# SCH-1.net
KiCad netlist of a schematic drawn in Altium Designer
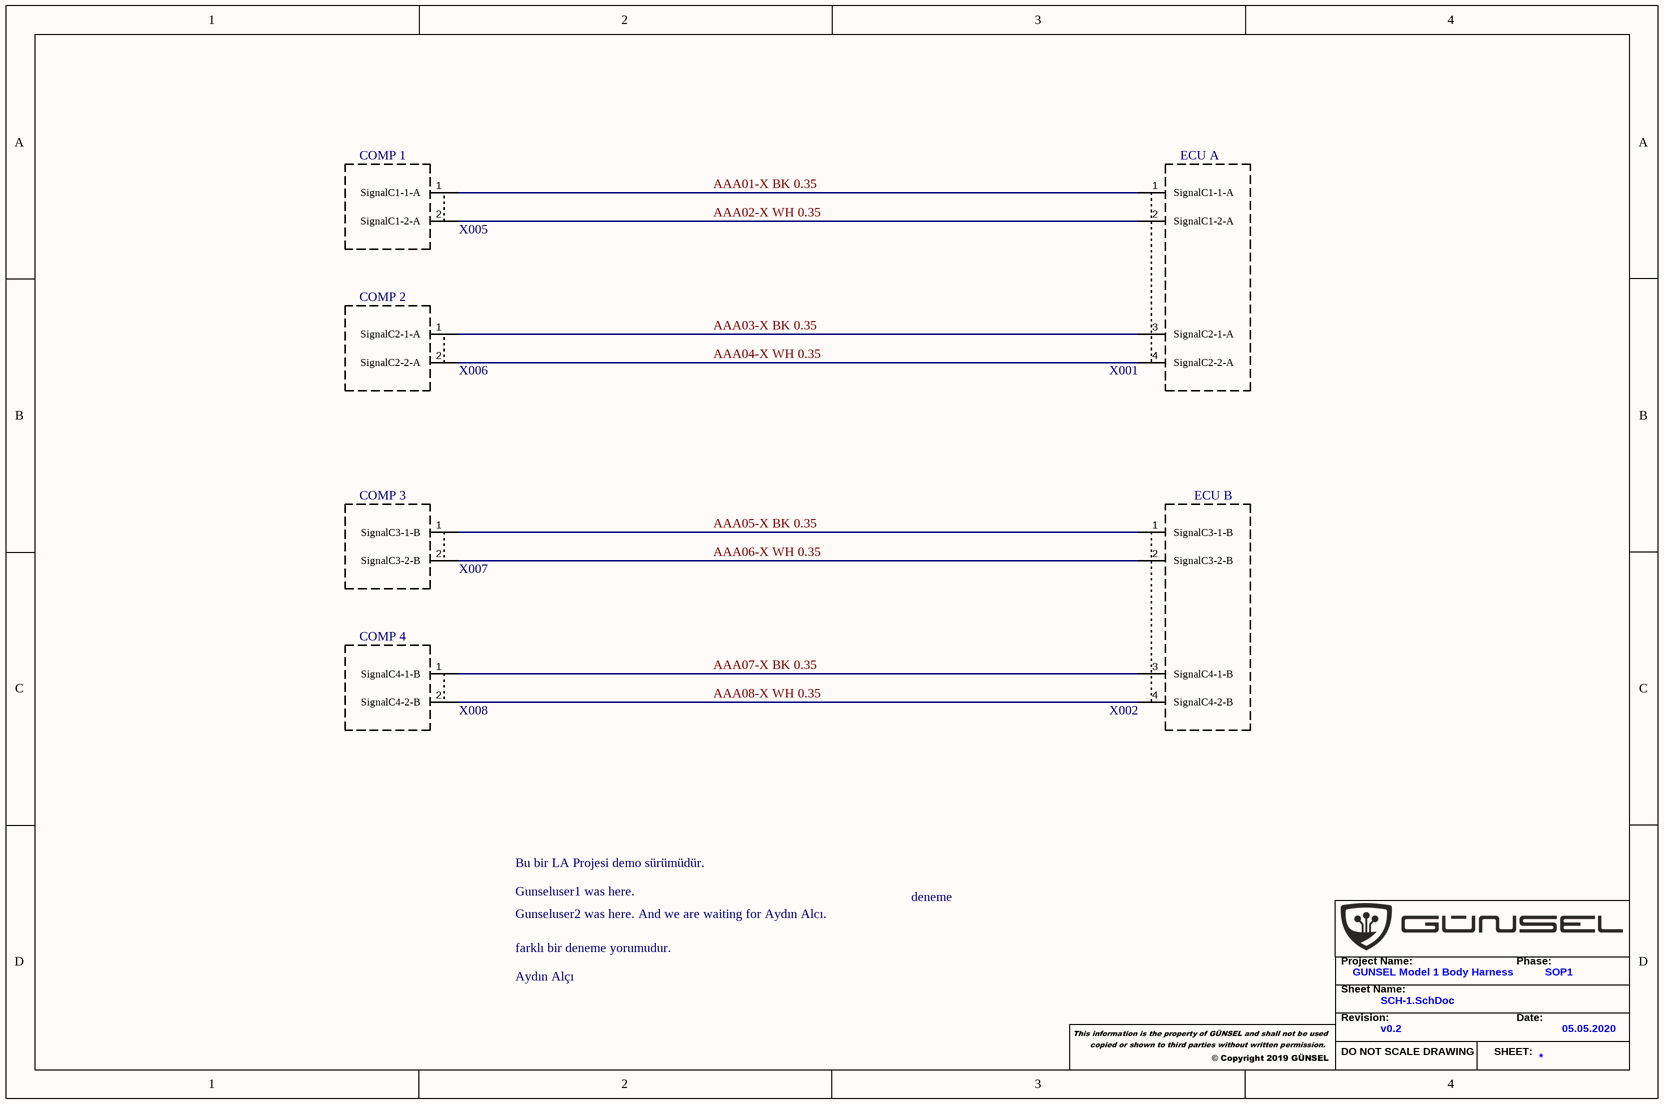
[diagram p0: SCH-1.SchDoc]

(export (version "E")
  (design (tool "Eeschema 10.0.6"))
  (components
    (comp (ref "X1")
      (value "X001")
      (fields (field (name "MANUFACTURER PART NUMBER") "E-1"))
      (libsource (lib "Günsel B9 LA Project Database Library") (part "E-1"))
    )
    (comp (ref "X2")
      (value "X005")
      (fields (field (name "MANUFACTURER PART NUMBER") "C-1"))
      (libsource (lib "Günsel B9 LA Project Database Library") (part "C-1"))
    )
    (comp (ref "X3")
      (value "X006")
      (fields (field (name "MANUFACTURER PART NUMBER") "C-2"))
      (libsource (lib "Günsel B9 LA Project Database Library") (part "C-2"))
    )
    (comp (ref "X4")
      (value "X002")
      (fields (field (name "MANUFACTURER PART NUMBER") "E-2"))
      (libsource (lib "Günsel B9 LA Project Database Library") (part "E-2"))
    )
    (comp (ref "X5")
      (value "X007")
      (fields (field (name "MANUFACTURER PART NUMBER") "C-3"))
      (libsource (lib "Günsel B9 LA Project Database Library") (part "C-3"))
    )
    (comp (ref "X6")
      (value "X008")
      (fields (field (name "MANUFACTURER PART NUMBER") "C-4"))
      (libsource (lib "Günsel B9 LA Project Database Library") (part "C-4"))
    )
  )
  (nets
    (net (code "1") (name "/AAA01-X BK 0.35") (class "Default")
      (node (ref "X1") (pin "1") (pinfunction "SignalC1-1-A_1") (pintype "passive"))
      (node (ref "X2") (pin "1") (pinfunction "SignalC1-1-A_1") (pintype "passive"))
    )
    (net (code "2") (name "/AAA02-X WH 0.35") (class "Default")
      (node (ref "X1") (pin "2") (pinfunction "SignalC1-2-A_2") (pintype "passive"))
      (node (ref "X2") (pin "2") (pinfunction "SignalC1-2-A_2") (pintype "passive"))
    )
    (net (code "3") (name "/AAA03-X BK 0.35") (class "Default")
      (node (ref "X1") (pin "3") (pinfunction "SignalC2-1-A_3") (pintype "passive"))
      (node (ref "X3") (pin "1") (pinfunction "SignalC2-1-A_1") (pintype "passive"))
    )
    (net (code "4") (name "/AAA04-X WH 0.35") (class "Default")
      (node (ref "X1") (pin "4") (pinfunction "SignalC2-2-A_4") (pintype "passive"))
      (node (ref "X3") (pin "2") (pinfunction "SignalC2-2-A_2") (pintype "passive"))
    )
    (net (code "5") (name "/AAA05-X BK 0.35") (class "Default")
      (node (ref "X4") (pin "1") (pinfunction "SignalC3-1-B_1") (pintype "passive"))
      (node (ref "X5") (pin "1") (pinfunction "SignalC3-1-B_1") (pintype "passive"))
    )
    (net (code "6") (name "/AAA06-X WH 0.35") (class "Default")
      (node (ref "X4") (pin "2") (pinfunction "SignalC3-2-B_2") (pintype "passive"))
      (node (ref "X5") (pin "2") (pinfunction "SignalC3-2-B_2") (pintype "passive"))
    )
    (net (code "7") (name "/AAA07-X BK 0.35") (class "Default")
      (node (ref "X4") (pin "3") (pinfunction "SignalC4-1-B_3") (pintype "passive"))
      (node (ref "X6") (pin "1") (pinfunction "SignalC4-1-B_1") (pintype "passive"))
    )
    (net (code "8") (name "/AAA08-X WH 0.35") (class "Default")
      (node (ref "X4") (pin "4") (pinfunction "SignalC4-2-B_4") (pintype "passive"))
      (node (ref "X6") (pin "2") (pinfunction "SignalC4-2-B_2") (pintype "passive"))
    )
    (net (code "9") (name "unconnected-(X1-Pad5)") (class "Default")
      (node (ref "X1") (pin "5") (pintype "passive"))
    )
    (net (code "10") (name "unconnected-(X1-Pad6)") (class "Default")
      (node (ref "X1") (pin "6") (pintype "passive"))
    )
    (net (code "11") (name "unconnected-(X1-Pad7)") (class "Default")
      (node (ref "X1") (pin "7") (pintype "passive"))
    )
    (net (code "12") (name "unconnected-(X1-Pad8)") (class "Default")
      (node (ref "X1") (pin "8") (pintype "passive"))
    )
    (net (code "13") (name "unconnected-(X1-Pad9)") (class "Default")
      (node (ref "X1") (pin "9") (pintype "passive"))
    )
    (net (code "14") (name "unconnected-(X1-Pad10)") (class "Default")
      (node (ref "X1") (pin "10") (pintype "passive"))
    )
    (net (code "15") (name "unconnected-(X1-Pad11)") (class "Default")
      (node (ref "X1") (pin "11") (pintype "passive"))
    )
    (net (code "16") (name "unconnected-(X1-Pad12)") (class "Default")
      (node (ref "X1") (pin "12") (pintype "passive"))
    )
    (net (code "17") (name "unconnected-(X1-Pad13)") (class "Default")
      (node (ref "X1") (pin "13") (pintype "passive"))
    )
    (net (code "18") (name "unconnected-(X1-Pad14)") (class "Default")
      (node (ref "X1") (pin "14") (pintype "passive"))
    )
    (net (code "19") (name "unconnected-(X1-Pad15)") (class "Default")
      (node (ref "X1") (pin "15") (pintype "passive"))
    )
    (net (code "20") (name "unconnected-(X1-Pad16)") (class "Default")
      (node (ref "X1") (pin "16") (pintype "passive"))
    )
    (net (code "21") (name "unconnected-(X1-Pad17)") (class "Default")
      (node (ref "X1") (pin "17") (pintype "passive"))
    )
    (net (code "22") (name "unconnected-(X1-Pad18)") (class "Default")
      (node (ref "X1") (pin "18") (pintype "passive"))
    )
    (net (code "23") (name "unconnected-(X1-Pad19)") (class "Default")
      (node (ref "X1") (pin "19") (pintype "passive"))
    )
    (net (code "24") (name "unconnected-(X1-Pad20)") (class "Default")
      (node (ref "X1") (pin "20") (pintype "passive"))
    )
    (net (code "25") (name "unconnected-(X2-Pad3)") (class "Default")
      (node (ref "X2") (pin "3") (pintype "passive"))
    )
    (net (code "26") (name "unconnected-(X2-Pad4)") (class "Default")
      (node (ref "X2") (pin "4") (pintype "passive"))
    )
    (net (code "27") (name "unconnected-(X2-Pad5)") (class "Default")
      (node (ref "X2") (pin "5") (pintype "passive"))
    )
    (net (code "28") (name "unconnected-(X3-Pad4)") (class "Default")
      (node (ref "X3") (pin "4") (pintype "passive"))
    )
    (net (code "29") (name "unconnected-(X3-Pad5)") (class "Default")
      (node (ref "X3") (pin "5") (pintype "passive"))
    )
    (net (code "30") (name "unconnected-(X3-SHT-CRC-1-Pad3)") (class "Default")
      (node (ref "X3") (pin "3") (pinfunction "SHT-CRC-1_3") (pintype "passive"))
    )
    (net (code "31") (name "unconnected-(X4-Pad5)") (class "Default")
      (node (ref "X4") (pin "5") (pinfunction "5_5") (pintype "passive"))
    )
    (net (code "32") (name "unconnected-(X4-Pad6)") (class "Default")
      (node (ref "X4") (pin "6") (pinfunction "6_6") (pintype "passive"))
    )
    (net (code "33") (name "unconnected-(X4-Pad7)") (class "Default")
      (node (ref "X4") (pin "7") (pinfunction "7_7") (pintype "passive"))
    )
    (net (code "34") (name "unconnected-(X4-Pad8)") (class "Default")
      (node (ref "X4") (pin "8") (pinfunction "8_8") (pintype "passive"))
    )
    (net (code "35") (name "unconnected-(X4-Pad9)") (class "Default")
      (node (ref "X4") (pin "9") (pinfunction "9_9") (pintype "passive"))
    )
    (net (code "36") (name "unconnected-(X4-Pad10)") (class "Default")
      (node (ref "X4") (pin "10") (pinfunction "10_10") (pintype "passive"))
    )
    (net (code "37") (name "unconnected-(X4-Pad11)") (class "Default")
      (node (ref "X4") (pin "11") (pinfunction "11_11") (pintype "passive"))
    )
    (net (code "38") (name "unconnected-(X4-Pad12)") (class "Default")
      (node (ref "X4") (pin "12") (pinfunction "12_12") (pintype "passive"))
    )
    (net (code "39") (name "unconnected-(X4-Pad13)") (class "Default")
      (node (ref "X4") (pin "13") (pinfunction "13_13") (pintype "passive"))
    )
    (net (code "40") (name "unconnected-(X4-Pad14)") (class "Default")
      (node (ref "X4") (pin "14") (pinfunction "14_14") (pintype "passive"))
    )
    (net (code "41") (name "unconnected-(X4-Pad15)") (class "Default")
      (node (ref "X4") (pin "15") (pinfunction "15_15") (pintype "passive"))
    )
    (net (code "42") (name "unconnected-(X4-Pad16)") (class "Default")
      (node (ref "X4") (pin "16") (pinfunction "16_16") (pintype "passive"))
    )
    (net (code "43") (name "unconnected-(X4-Pad17)") (class "Default")
      (node (ref "X4") (pin "17") (pinfunction "17_17") (pintype "passive"))
    )
    (net (code "44") (name "unconnected-(X4-Pad18)") (class "Default")
      (node (ref "X4") (pin "18") (pinfunction "18_18") (pintype "passive"))
    )
    (net (code "45") (name "unconnected-(X4-Pad19)") (class "Default")
      (node (ref "X4") (pin "19") (pinfunction "19_19") (pintype "passive"))
    )
    (net (code "46") (name "unconnected-(X4-Pad20)") (class "Default")
      (node (ref "X4") (pin "20") (pinfunction "20_20") (pintype "passive"))
    )
    (net (code "47") (name "unconnected-(X5-Pad3)") (class "Default")
      (node (ref "X5") (pin "3") (pinfunction "3_3") (pintype "passive"))
    )
    (net (code "48") (name "unconnected-(X5-Pad4)") (class "Default")
      (node (ref "X5") (pin "4") (pinfunction "4_4") (pintype "passive"))
    )
    (net (code "49") (name "unconnected-(X5-Pad5)") (class "Default")
      (node (ref "X5") (pin "5") (pinfunction "5_5") (pintype "passive"))
    )
    (net (code "50") (name "unconnected-(X6-SHT-CRC-2-Pad3)") (class "Default")
      (node (ref "X6") (pin "3") (pinfunction "SHT-CRC-2_3") (pintype "passive"))
    )
    (net (code "51") (name "unconnected-(X6-SHT-CRC-3-Pad4)") (class "Default")
      (node (ref "X6") (pin "4") (pinfunction "SHT-CRC-3_4") (pintype "passive"))
    )
    (net (code "52") (name "unconnected-(X6-SHT-CRC-4-Pad5)") (class "Default")
      (node (ref "X6") (pin "5") (pinfunction "SHT-CRC-4_5") (pintype "passive"))
    )
  )
)
